# Curret_Detector_V2.net
KiCad netlist of a schematic drawn in EAGLE
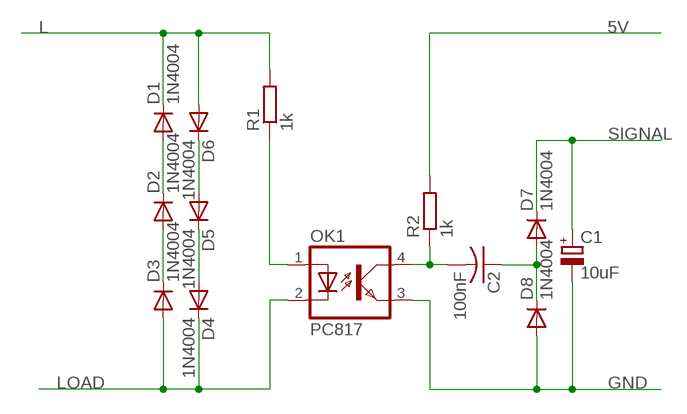
[diagram p0: schematic, sheet 1]

(export (version "E")
  (design (tool "Eeschema 10.0.6"))
  (components
    (comp (ref "C1")
      (value "10uF")
      (footprint "eagle-import:E2,5-7")
      (libsource (lib "eagle-import") (part "CPOL-EUE2.5-7"))
    )
    (comp (ref "C2")
      (value "100nF")
      (footprint "eagle-import:C050-035X075")
      (libsource (lib "eagle-import") (part "C-US050-035X075"))
    )
    (comp (ref "D1")
      (value "1N4004")
      (footprint "eagle-import:DO41-10")
      (libsource (lib "eagle-import") (part "1N4004"))
    )
    (comp (ref "D2")
      (value "1N4004")
      (footprint "eagle-import:DO41-10")
      (libsource (lib "eagle-import") (part "1N4004"))
    )
    (comp (ref "D3")
      (value "1N4004")
      (footprint "eagle-import:DO41-10")
      (libsource (lib "eagle-import") (part "1N4004"))
    )
    (comp (ref "D4")
      (value "1N4004")
      (footprint "eagle-import:DO41-10")
      (libsource (lib "eagle-import") (part "1N4004"))
    )
    (comp (ref "D5")
      (value "1N4004")
      (footprint "eagle-import:DO41-10")
      (libsource (lib "eagle-import") (part "1N4004"))
    )
    (comp (ref "D6")
      (value "1N4004")
      (footprint "eagle-import:DO41-10")
      (libsource (lib "eagle-import") (part "1N4004"))
    )
    (comp (ref "D7")
      (value "1N4004")
      (footprint "eagle-import:DO41-10")
      (libsource (lib "eagle-import") (part "1N4004"))
    )
    (comp (ref "D8")
      (value "1N4004")
      (footprint "eagle-import:DO41-10")
      (libsource (lib "eagle-import") (part "1N4004"))
    )
    (comp (ref "OK1")
      (value "PC817")
      (footprint "eagle-import:DIL04")
      (libsource (lib "eagle-import") (part "PC817"))
    )
    (comp (ref "R1")
      (value "1k")
      (footprint "eagle-import:0207_10")
      (libsource (lib "eagle-import") (part "R-EU_0207/10"))
    )
    (comp (ref "R2")
      (value "1k")
      (footprint "eagle-import:0207_10")
      (libsource (lib "eagle-import") (part "R-EU_0207/10"))
    )
  )
  (nets
    (net (code "1") (name "/5V") (class "Default")
      (node (ref "R2") (pin "2") (pinfunction "2_2") (pintype "passive"))
    )
    (net (code "2") (name "/GND") (class "Default")
      (node (ref "C1") (pin "-") (pinfunction "-_-") (pintype "passive"))
      (node (ref "D8") (pin "A") (pinfunction "A_A") (pintype "passive"))
      (node (ref "OK1") (pin "3") (pinfunction "EMIT_3") (pintype "passive"))
    )
    (net (code "3") (name "/L") (class "Default")
      (node (ref "D1") (pin "C") (pinfunction "C_C") (pintype "passive"))
      (node (ref "D6") (pin "A") (pinfunction "A_A") (pintype "passive"))
      (node (ref "R1") (pin "2") (pinfunction "2_2") (pintype "passive"))
    )
    (net (code "4") (name "/LOAD") (class "Default")
      (node (ref "D3") (pin "A") (pinfunction "A_A") (pintype "passive"))
      (node (ref "D4") (pin "C") (pinfunction "C_C") (pintype "passive"))
      (node (ref "OK1") (pin "2") (pinfunction "C_2") (pintype "passive"))
    )
    (net (code "5") (name "/SIGNAL") (class "Default")
      (node (ref "C1") (pin "+") (pinfunction "+_+") (pintype "passive"))
      (node (ref "D7") (pin "C") (pinfunction "C_C") (pintype "passive"))
    )
    (net (code "6") (name "Net-(C2-Pad1)") (class "Default")
      (node (ref "C2") (pin "1") (pinfunction "1_1") (pintype "passive"))
      (node (ref "D7") (pin "A") (pinfunction "A_A") (pintype "passive"))
      (node (ref "D8") (pin "C") (pinfunction "C_C") (pintype "passive"))
    )
    (net (code "7") (name "Net-(D1-PadA)") (class "Default")
      (node (ref "D1") (pin "A") (pinfunction "A_A") (pintype "passive"))
      (node (ref "D2") (pin "C") (pinfunction "C_C") (pintype "passive"))
    )
    (net (code "8") (name "Net-(D2-PadA)") (class "Default")
      (node (ref "D2") (pin "A") (pinfunction "A_A") (pintype "passive"))
      (node (ref "D3") (pin "C") (pinfunction "C_C") (pintype "passive"))
    )
    (net (code "9") (name "Net-(D4-PadA)") (class "Default")
      (node (ref "D4") (pin "A") (pinfunction "A_A") (pintype "passive"))
      (node (ref "D5") (pin "C") (pinfunction "C_C") (pintype "passive"))
    )
    (net (code "10") (name "Net-(D5-PadA)") (class "Default")
      (node (ref "D5") (pin "A") (pinfunction "A_A") (pintype "passive"))
      (node (ref "D6") (pin "C") (pinfunction "C_C") (pintype "passive"))
    )
    (net (code "11") (name "Net-(OK1-A)") (class "Default")
      (node (ref "OK1") (pin "1") (pinfunction "A_1") (pintype "passive"))
      (node (ref "R1") (pin "1") (pinfunction "1_1") (pintype "passive"))
    )
    (net (code "12") (name "Net-(OK1-COL)") (class "Default")
      (node (ref "C2") (pin "2") (pinfunction "2_2") (pintype "passive"))
      (node (ref "OK1") (pin "4") (pinfunction "COL_4") (pintype "passive"))
      (node (ref "R2") (pin "1") (pinfunction "1_1") (pintype "passive"))
    )
  )
)
